# tiles.net
KiCad netlist of a schematic drawn in EAGLE
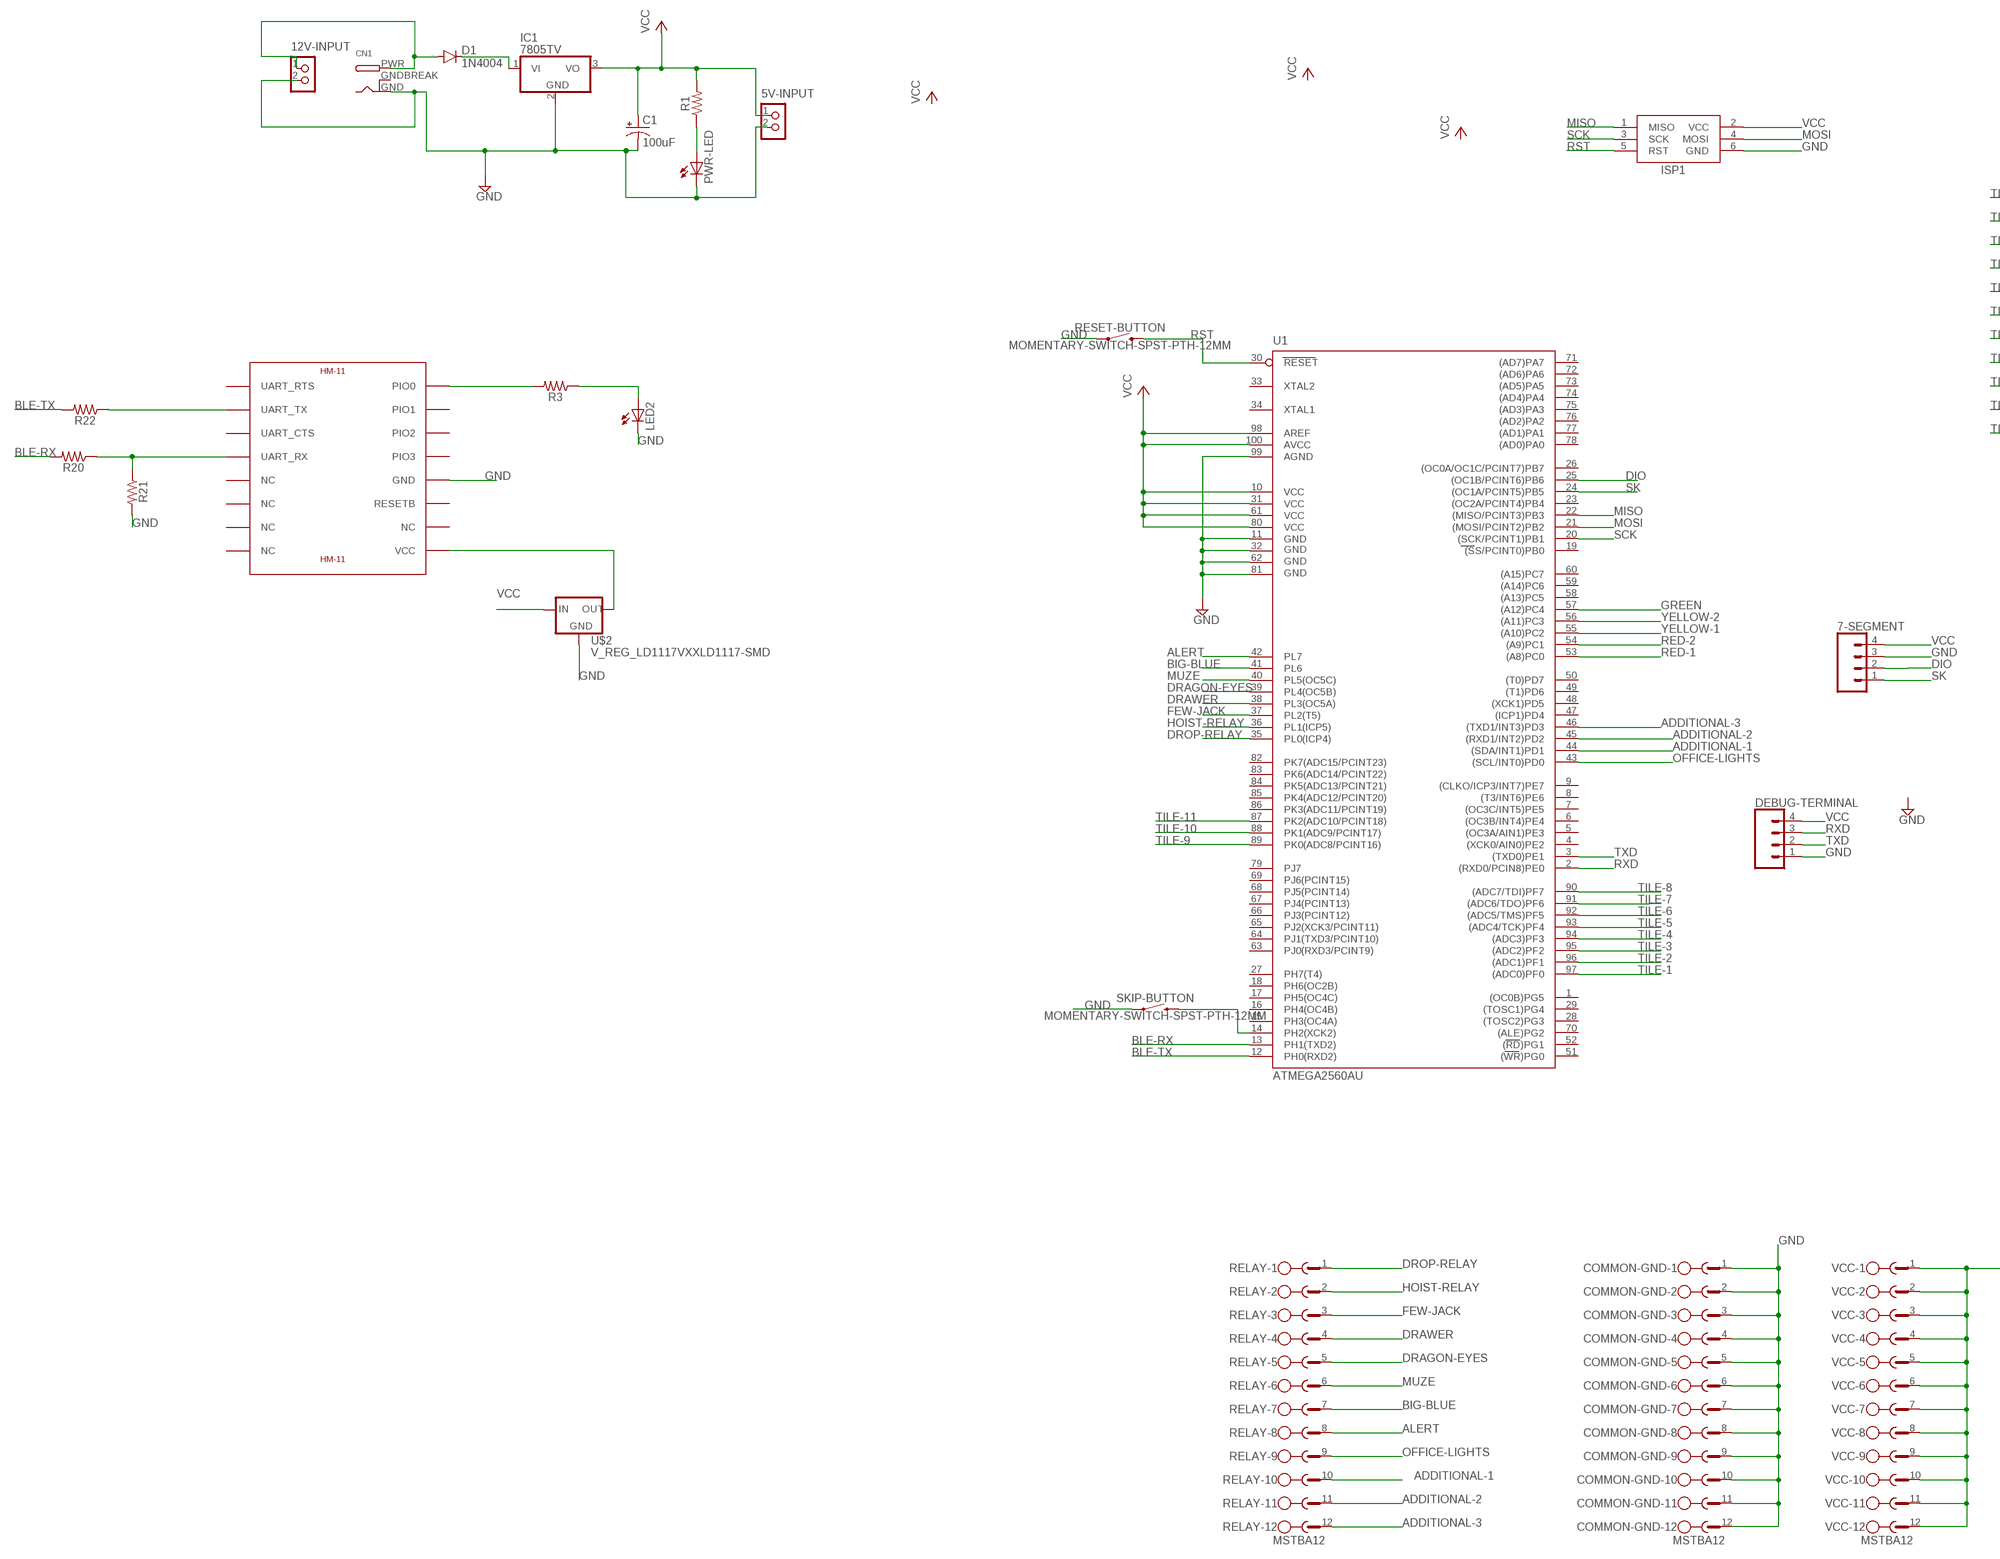
[diagram p0: schematic, sheet 1, part 1 of 2]
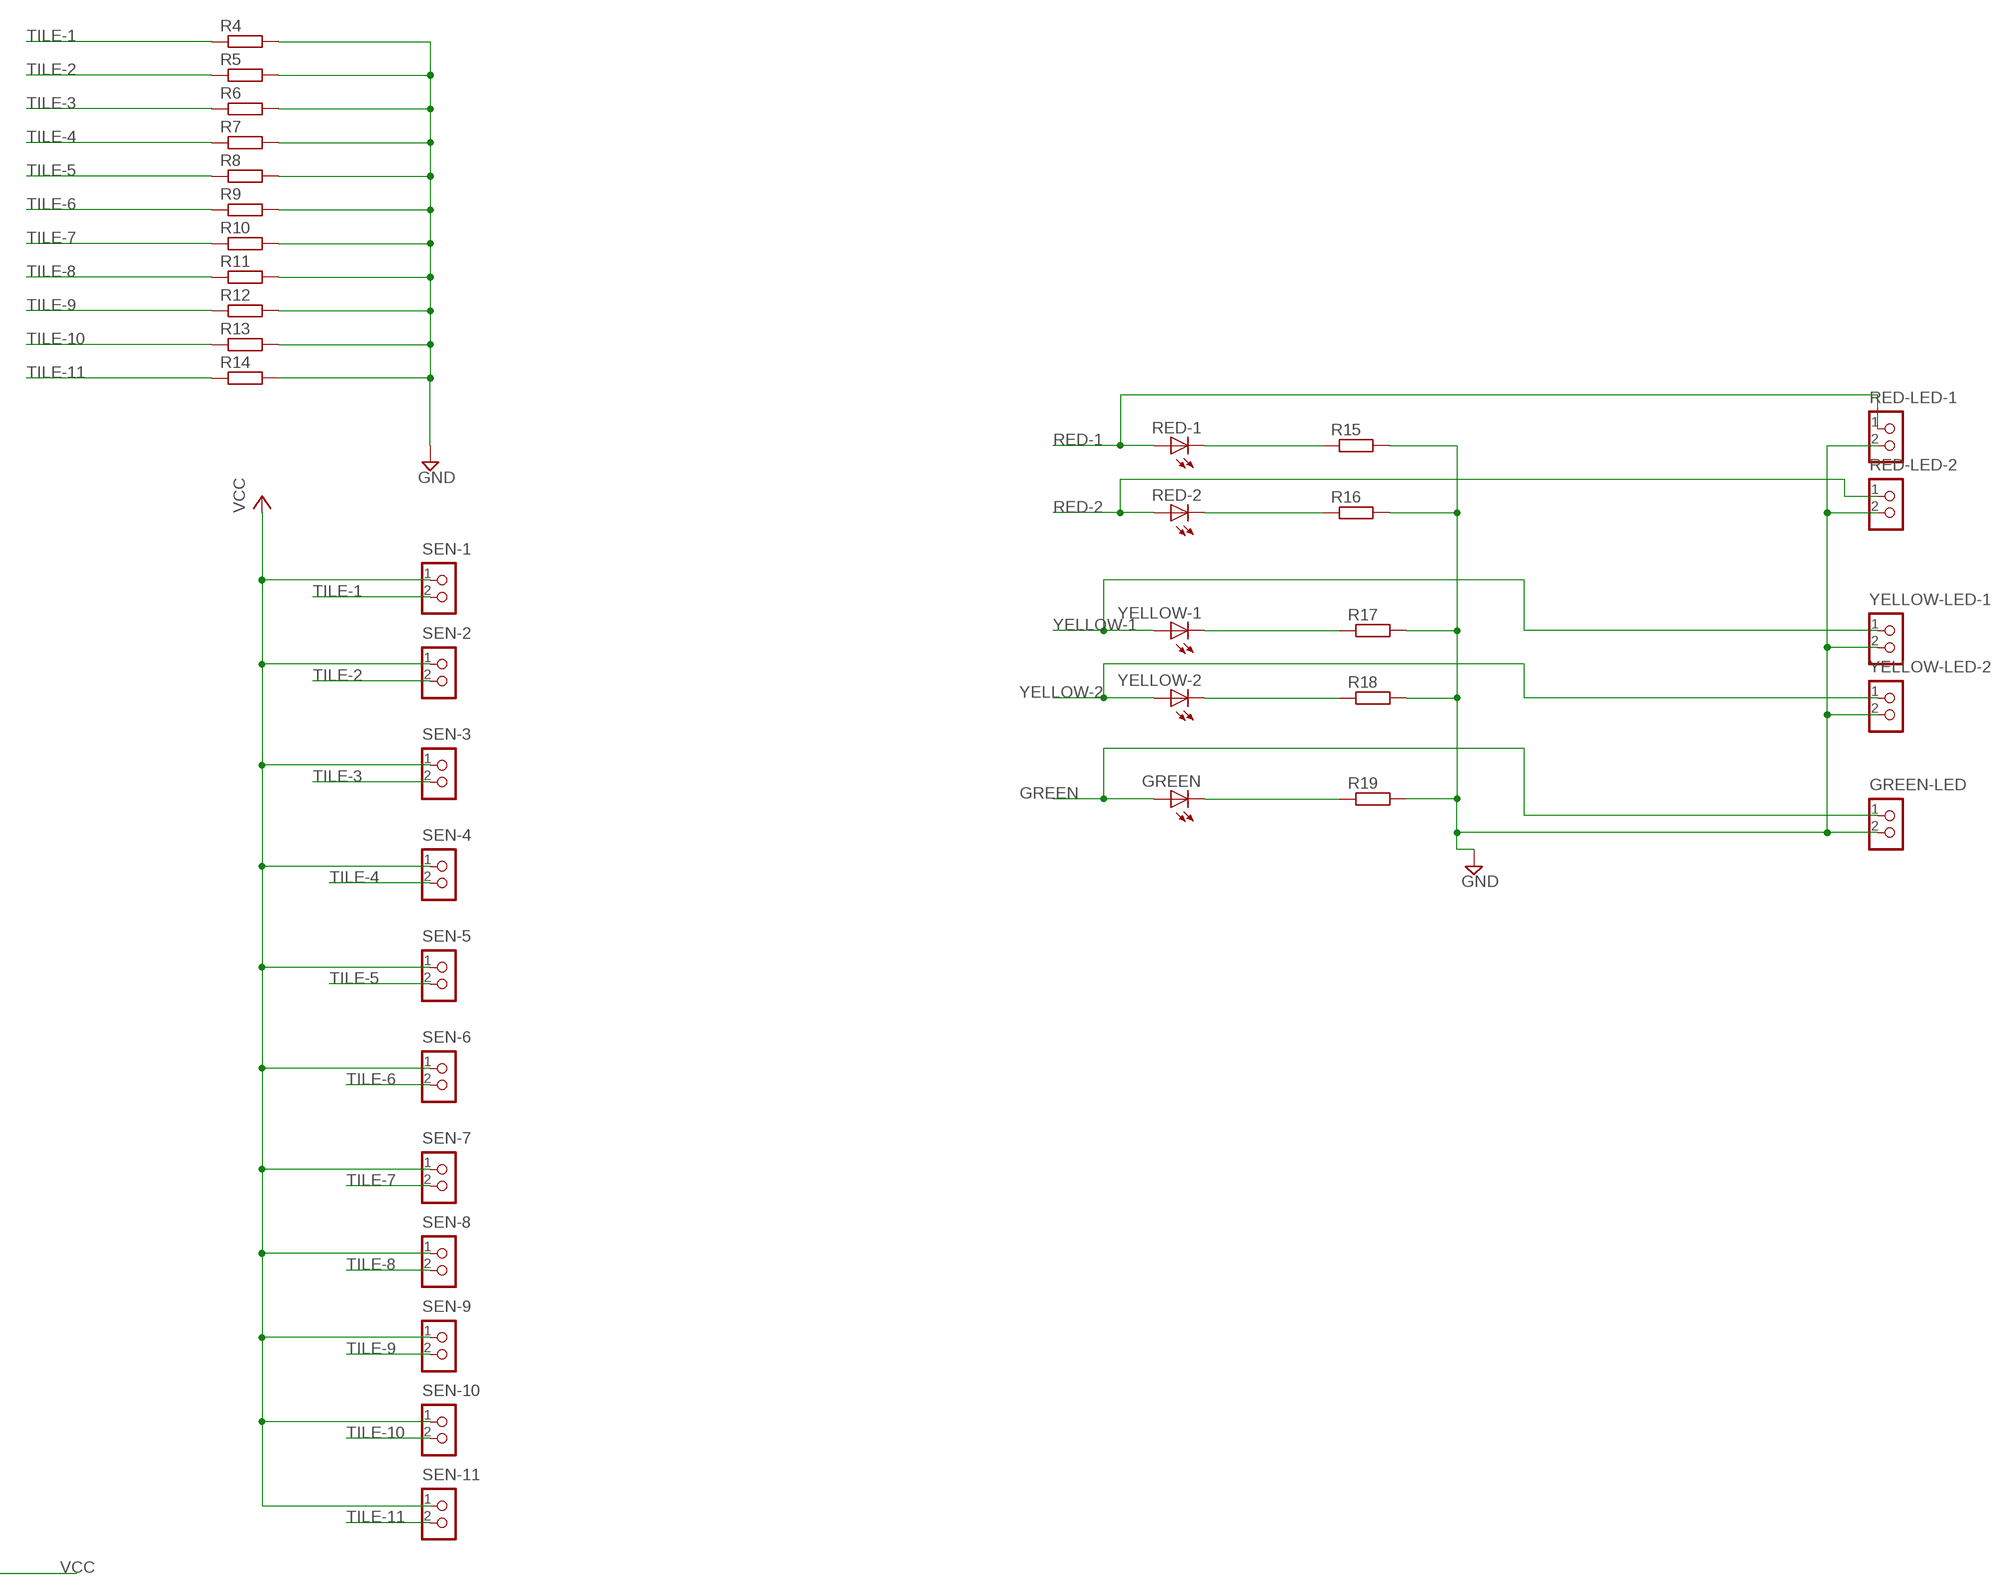
[diagram p1: schematic, sheet 1, part 2 of 2]

(export (version "E")
  (design (tool "Eeschema 10.0.6"))
  (components
    (comp (ref "5V-INPUT")
      (value "CON_TERMINAL_BLOCK_02-5MM")
      (footprint "eagle-import:TERMINAL_BLOCK_2P_5")
      (libsource (lib "eagle-import") (part "CON_TERMINAL_BLOCK_02-5MM"))
    )
    (comp (ref "7-SEGMENT")
      (value "CONN_04PTH")
      (footprint "eagle-import:1X04")
      (libsource (lib "eagle-import") (part "CONN_04PTH"))
    )
    (comp (ref "12V-INPUT")
      (value "CON_TERMINAL_BLOCK_02-5MM")
      (footprint "eagle-import:TERMINAL_BLOCK_2P_5")
      (libsource (lib "eagle-import") (part "CON_TERMINAL_BLOCK_02-5MM"))
    )
    (comp (ref "C1")
      (value "100uF")
      (footprint "eagle-import:CPOL-RADIAL-2.5MM-6.5MM")
      (libsource (lib "eagle-import") (part "100UF-POLAR-RADIAL-2.5MM-25V-20%"))
    )
    (comp (ref "CN1")
      (value "DCBARRELPTH")
      (footprint "eagle-import:DCJACK_2MM_PTH")
      (libsource (lib "eagle-import") (part "DCBARRELPTH"))
    )
    (comp (ref "COMMON-GND")
      (value "MSTBA12")
      (footprint "eagle-import:MSTBA12")
      (fields (field (name "MPN") "1757349"))
      (libsource (lib "eagle-import") (part "MSTBA12"))
    )
    (comp (ref "D1")
      (value "1N4004")
      (footprint "eagle-import:DO41-10")
      (libsource (lib "eagle-import") (part "1N4004"))
    )
    (comp (ref "DEBUG-TERMINAL")
      (value "CONN_04PTH")
      (footprint "eagle-import:1X04")
      (libsource (lib "eagle-import") (part "CONN_04PTH"))
    )
    (comp (ref "GREEN")
      (value "LED5MM")
      (footprint "eagle-import:LED5MM")
      (libsource (lib "eagle-import") (part "LED5MM"))
    )
    (comp (ref "GREEN-LED")
      (value "CON_TERMINAL_BLOCK_02-5MM")
      (footprint "eagle-import:TERMINAL_BLOCK_2P_5")
      (libsource (lib "eagle-import") (part "CON_TERMINAL_BLOCK_02-5MM"))
    )
    (comp (ref "IC1")
      (value "7805TV")
      (footprint "eagle-import:TO220V")
      (libsource (lib "eagle-import") (part "78TV05"))
    )
    (comp (ref "ISP1")
      (value "AVRISP-6")
      (footprint "eagle-import:AVRISP")
      (libsource (lib "eagle-import") (part "AVRISP-6"))
    )
    (comp (ref "LED2")
      (value "LED1206")
      (footprint "eagle-import:LED-1206")
      (libsource (lib "eagle-import") (part "LED1206"))
    )
    (comp (ref "PWR-LED")
      (value "LED1206")
      (footprint "eagle-import:LED-1206")
      (libsource (lib "eagle-import") (part "LED1206"))
    )
    (comp (ref "R1")
      (value "RESISTOR1206")
      (footprint "eagle-import:1206")
      (fields (field (name "SPICEPREFIX") "R"))
      (libsource (lib "eagle-import") (part "RESISTOR1206"))
    )
    (comp (ref "R3")
      (value "RESISTOR1206")
      (footprint "eagle-import:1206")
      (fields (field (name "SPICEPREFIX") "R"))
      (libsource (lib "eagle-import") (part "RESISTOR1206"))
    )
    (comp (ref "R4")
      (value "R-EU_0204/7")
      (footprint "eagle-import:0204_7")
      (libsource (lib "eagle-import") (part "R-EU_0204/7"))
    )
    (comp (ref "R5")
      (value "R-EU_0204/7")
      (footprint "eagle-import:0204_7")
      (libsource (lib "eagle-import") (part "R-EU_0204/7"))
    )
    (comp (ref "R6")
      (value "R-EU_0204/7")
      (footprint "eagle-import:0204_7")
      (libsource (lib "eagle-import") (part "R-EU_0204/7"))
    )
    (comp (ref "R7")
      (value "R-EU_0204/7")
      (footprint "eagle-import:0204_7")
      (libsource (lib "eagle-import") (part "R-EU_0204/7"))
    )
    (comp (ref "R8")
      (value "R-EU_0204/7")
      (footprint "eagle-import:0204_7")
      (libsource (lib "eagle-import") (part "R-EU_0204/7"))
    )
    (comp (ref "R9")
      (value "R-EU_0204/7")
      (footprint "eagle-import:0204_7")
      (libsource (lib "eagle-import") (part "R-EU_0204/7"))
    )
    (comp (ref "R10")
      (value "R-EU_0204/7")
      (footprint "eagle-import:0204_7")
      (libsource (lib "eagle-import") (part "R-EU_0204/7"))
    )
    (comp (ref "R11")
      (value "R-EU_0204/7")
      (footprint "eagle-import:0204_7")
      (libsource (lib "eagle-import") (part "R-EU_0204/7"))
    )
    (comp (ref "R12")
      (value "R-EU_0204/7")
      (footprint "eagle-import:0204_7")
      (libsource (lib "eagle-import") (part "R-EU_0204/7"))
    )
    (comp (ref "R13")
      (value "R-EU_0204/7")
      (footprint "eagle-import:0204_7")
      (libsource (lib "eagle-import") (part "R-EU_0204/7"))
    )
    (comp (ref "R14")
      (value "R-EU_0204/7")
      (footprint "eagle-import:0204_7")
      (libsource (lib "eagle-import") (part "R-EU_0204/7"))
    )
    (comp (ref "R15")
      (value "R-EU_0204/7")
      (footprint "eagle-import:0204_7")
      (libsource (lib "eagle-import") (part "R-EU_0204/7"))
    )
    (comp (ref "R16")
      (value "R-EU_0204/7")
      (footprint "eagle-import:0204_7")
      (libsource (lib "eagle-import") (part "R-EU_0204/7"))
    )
    (comp (ref "R17")
      (value "R-EU_0204/7")
      (footprint "eagle-import:0204_7")
      (libsource (lib "eagle-import") (part "R-EU_0204/7"))
    )
    (comp (ref "R18")
      (value "R-EU_0204/7")
      (footprint "eagle-import:0204_7")
      (libsource (lib "eagle-import") (part "R-EU_0204/7"))
    )
    (comp (ref "R19")
      (value "R-EU_0204/7")
      (footprint "eagle-import:0204_7")
      (libsource (lib "eagle-import") (part "R-EU_0204/7"))
    )
    (comp (ref "R20")
      (value "RESISTOR1206")
      (footprint "eagle-import:1206")
      (fields (field (name "SPICEPREFIX") "R"))
      (libsource (lib "eagle-import") (part "RESISTOR1206"))
    )
    (comp (ref "R21")
      (value "RESISTOR1206")
      (footprint "eagle-import:1206")
      (fields (field (name "SPICEPREFIX") "R"))
      (libsource (lib "eagle-import") (part "RESISTOR1206"))
    )
    (comp (ref "R22")
      (value "RESISTOR1206")
      (footprint "eagle-import:1206")
      (fields (field (name "SPICEPREFIX") "R"))
      (libsource (lib "eagle-import") (part "RESISTOR1206"))
    )
    (comp (ref "RED-1")
      (value "LED5MM")
      (footprint "eagle-import:LED5MM")
      (libsource (lib "eagle-import") (part "LED5MM"))
    )
    (comp (ref "RED-2")
      (value "LED5MM")
      (footprint "eagle-import:LED5MM")
      (libsource (lib "eagle-import") (part "LED5MM"))
    )
    (comp (ref "RED-LED-1")
      (value "CON_TERMINAL_BLOCK_02-5MM")
      (footprint "eagle-import:TERMINAL_BLOCK_2P_5")
      (libsource (lib "eagle-import") (part "CON_TERMINAL_BLOCK_02-5MM"))
    )
    (comp (ref "RED-LED-2")
      (value "CON_TERMINAL_BLOCK_02-5MM")
      (footprint "eagle-import:TERMINAL_BLOCK_2P_5")
      (libsource (lib "eagle-import") (part "CON_TERMINAL_BLOCK_02-5MM"))
    )
    (comp (ref "RELAY")
      (value "MSTBA12")
      (footprint "eagle-import:MSTBA12")
      (fields (field (name "MPN") "1757349"))
      (libsource (lib "eagle-import") (part "MSTBA12"))
    )
    (comp (ref "RESET-BUTTON")
      (value "MOMENTARY-SWITCH-SPST-PTH-12MM")
      (footprint "eagle-import:TACTILE_SWITCH_PTH_12MM")
      (libsource (lib "eagle-import") (part "MOMENTARY-SWITCH-SPST-PTH-12MM"))
    )
    (comp (ref "SEN-1")
      (value "CON_TERMINAL_BLOCK_02-5MM")
      (footprint "eagle-import:TERMINAL_BLOCK_2P_5")
      (libsource (lib "eagle-import") (part "CON_TERMINAL_BLOCK_02-5MM"))
    )
    (comp (ref "SEN-2")
      (value "CON_TERMINAL_BLOCK_02-5MM")
      (footprint "eagle-import:TERMINAL_BLOCK_2P_5")
      (libsource (lib "eagle-import") (part "CON_TERMINAL_BLOCK_02-5MM"))
    )
    (comp (ref "SEN-3")
      (value "CON_TERMINAL_BLOCK_02-5MM")
      (footprint "eagle-import:TERMINAL_BLOCK_2P_5")
      (libsource (lib "eagle-import") (part "CON_TERMINAL_BLOCK_02-5MM"))
    )
    (comp (ref "SEN-4")
      (value "CON_TERMINAL_BLOCK_02-5MM")
      (footprint "eagle-import:TERMINAL_BLOCK_2P_5")
      (libsource (lib "eagle-import") (part "CON_TERMINAL_BLOCK_02-5MM"))
    )
    (comp (ref "SEN-5")
      (value "CON_TERMINAL_BLOCK_02-5MM")
      (footprint "eagle-import:TERMINAL_BLOCK_2P_5")
      (libsource (lib "eagle-import") (part "CON_TERMINAL_BLOCK_02-5MM"))
    )
    (comp (ref "SEN-6")
      (value "CON_TERMINAL_BLOCK_02-5MM")
      (footprint "eagle-import:TERMINAL_BLOCK_2P_5")
      (libsource (lib "eagle-import") (part "CON_TERMINAL_BLOCK_02-5MM"))
    )
    (comp (ref "SEN-7")
      (value "CON_TERMINAL_BLOCK_02-5MM")
      (footprint "eagle-import:TERMINAL_BLOCK_2P_5")
      (libsource (lib "eagle-import") (part "CON_TERMINAL_BLOCK_02-5MM"))
    )
    (comp (ref "SEN-8")
      (value "CON_TERMINAL_BLOCK_02-5MM")
      (footprint "eagle-import:TERMINAL_BLOCK_2P_5")
      (libsource (lib "eagle-import") (part "CON_TERMINAL_BLOCK_02-5MM"))
    )
    (comp (ref "SEN-9")
      (value "CON_TERMINAL_BLOCK_02-5MM")
      (footprint "eagle-import:TERMINAL_BLOCK_2P_5")
      (libsource (lib "eagle-import") (part "CON_TERMINAL_BLOCK_02-5MM"))
    )
    (comp (ref "SEN-10")
      (value "CON_TERMINAL_BLOCK_02-5MM")
      (footprint "eagle-import:TERMINAL_BLOCK_2P_5")
      (libsource (lib "eagle-import") (part "CON_TERMINAL_BLOCK_02-5MM"))
    )
    (comp (ref "SEN-11")
      (value "CON_TERMINAL_BLOCK_02-5MM")
      (footprint "eagle-import:TERMINAL_BLOCK_2P_5")
      (libsource (lib "eagle-import") (part "CON_TERMINAL_BLOCK_02-5MM"))
    )
    (comp (ref "SKIP-BUTTON")
      (value "MOMENTARY-SWITCH-SPST-PTH-12MM")
      (footprint "eagle-import:TACTILE_SWITCH_PTH_12MM")
      (libsource (lib "eagle-import") (part "MOMENTARY-SWITCH-SPST-PTH-12MM"))
    )
    (comp (ref "U$1")
      (value "HM-11")
      (footprint "eagle-import:HM-11")
      (libsource (lib "eagle-import") (part "HM-11"))
    )
    (comp (ref "U$2")
      (value "V_REG_LD1117VXXLD1117-SMD")
      (footprint "eagle-import:SOT223")
      (fields (field (name "SPICEPREFIX") "U"))
      (libsource (lib "eagle-import") (part "V_REG_LD1117VXXLD1117-SMD"))
    )
    (comp (ref "U1")
      (value "ATMEGA2560AU")
      (footprint "eagle-import:TQFP100")
      (libsource (lib "eagle-import") (part "ATMEGA2560AU"))
    )
    (comp (ref "VCC")
      (value "MSTBA12")
      (footprint "eagle-import:MSTBA12")
      (fields (field (name "MPN") "1757349"))
      (libsource (lib "eagle-import") (part "MSTBA12"))
    )
    (comp (ref "YELLOW-1")
      (value "LED5MM")
      (footprint "eagle-import:LED5MM")
      (libsource (lib "eagle-import") (part "LED5MM"))
    )
    (comp (ref "YELLOW-2")
      (value "LED5MM")
      (footprint "eagle-import:LED5MM")
      (libsource (lib "eagle-import") (part "LED5MM"))
    )
    (comp (ref "YELLOW-LED-1")
      (value "CON_TERMINAL_BLOCK_02-5MM")
      (footprint "eagle-import:TERMINAL_BLOCK_2P_5")
      (libsource (lib "eagle-import") (part "CON_TERMINAL_BLOCK_02-5MM"))
    )
    (comp (ref "YELLOW-LED-2")
      (value "CON_TERMINAL_BLOCK_02-5MM")
      (footprint "eagle-import:TERMINAL_BLOCK_2P_5")
      (libsource (lib "eagle-import") (part "CON_TERMINAL_BLOCK_02-5MM"))
    )
  )
  (nets
    (net (code "1") (name "/ADDITIONAL-1") (class "Default")
      (node (ref "RELAY") (pin "10") (pinfunction "1_10") (pintype "passive"))
      (node (ref "U1") (pin "44") (pinfunction "(SDA/INT1)PD1_44") (pintype "bidirectional"))
    )
    (net (code "2") (name "/ADDITIONAL-2") (class "Default")
      (node (ref "RELAY") (pin "11") (pinfunction "1_11") (pintype "passive"))
      (node (ref "U1") (pin "45") (pinfunction "(RXD1/INT2)PD2_45") (pintype "bidirectional"))
    )
    (net (code "3") (name "/ADDITIONAL-3") (class "Default")
      (node (ref "RELAY") (pin "12") (pinfunction "1_12") (pintype "passive"))
      (node (ref "U1") (pin "46") (pinfunction "(TXD1/INT3)PD3_46") (pintype "bidirectional"))
    )
    (net (code "4") (name "/ALERT") (class "Default")
      (node (ref "RELAY") (pin "8") (pinfunction "1_8") (pintype "passive"))
      (node (ref "U1") (pin "42") (pinfunction "PL7_42") (pintype "bidirectional"))
    )
    (net (code "5") (name "/BIG-BLUE") (class "Default")
      (node (ref "RELAY") (pin "7") (pinfunction "1_7") (pintype "passive"))
      (node (ref "U1") (pin "41") (pinfunction "PL6_41") (pintype "bidirectional"))
    )
    (net (code "6") (name "/BLE-RX") (class "Default")
      (node (ref "R20") (pin "2") (pinfunction "2_2") (pintype "passive"))
      (node (ref "U1") (pin "13") (pinfunction "PH1(TXD2)_13") (pintype "bidirectional"))
    )
    (net (code "7") (name "/BLE-TX") (class "Default")
      (node (ref "R22") (pin "2") (pinfunction "2_2") (pintype "passive"))
      (node (ref "U1") (pin "12") (pinfunction "PH0(RXD2)_12") (pintype "bidirectional"))
    )
    (net (code "8") (name "/DIO") (class "Default")
      (node (ref "7-SEGMENT") (pin "2") (pinfunction "2_2") (pintype "passive"))
      (node (ref "U1") (pin "25") (pinfunction "(OC1B/PCINT6)PB6_25") (pintype "bidirectional"))
    )
    (net (code "9") (name "/DRAGON-EYES") (class "Default")
      (node (ref "RELAY") (pin "5") (pinfunction "1_5") (pintype "passive"))
      (node (ref "U1") (pin "39") (pinfunction "PL4(OC5B)_39") (pintype "bidirectional"))
    )
    (net (code "10") (name "/DRAWER") (class "Default")
      (node (ref "RELAY") (pin "4") (pinfunction "1_4") (pintype "passive"))
      (node (ref "U1") (pin "38") (pinfunction "PL3(OC5A)_38") (pintype "bidirectional"))
    )
    (net (code "11") (name "/DROP-RELAY") (class "Default")
      (node (ref "RELAY") (pin "1") (pinfunction "1_1") (pintype "passive"))
      (node (ref "U1") (pin "35") (pinfunction "PL0(ICP4)_35") (pintype "bidirectional"))
    )
    (net (code "12") (name "/FEW-JACK") (class "Default")
      (node (ref "RELAY") (pin "3") (pinfunction "1_3") (pintype "passive"))
      (node (ref "U1") (pin "37") (pinfunction "PL2(T5)_37") (pintype "bidirectional"))
    )
    (net (code "13") (name "/GNDBREAK") (class "Default")
      (node (ref "CN1") (pin "GNDBREAK") (pinfunction "GNDBREAK_GNDBREAK") (pintype "power_in"))
    )
    (net (code "14") (name "/GREEN") (class "Default")
      (node (ref "GREEN") (pin "A") (pinfunction "A_A") (pintype "passive"))
      (node (ref "GREEN-LED") (pin "1") (pinfunction "1_1") (pintype "passive"))
      (node (ref "U1") (pin "57") (pinfunction "(A12)PC4_57") (pintype "bidirectional"))
    )
    (net (code "15") (name "/HOIST-RELAY") (class "Default")
      (node (ref "RELAY") (pin "2") (pinfunction "1_2") (pintype "passive"))
      (node (ref "U1") (pin "36") (pinfunction "PL1(ICP5)_36") (pintype "bidirectional"))
    )
    (net (code "16") (name "/MISO") (class "Default")
      (node (ref "ISP1") (pin "1") (pinfunction "MISO_1") (pintype "input"))
      (node (ref "U1") (pin "22") (pinfunction "(MISO/PCINT3)PB3_22") (pintype "bidirectional"))
    )
    (net (code "17") (name "/MOSI") (class "Default")
      (node (ref "ISP1") (pin "4") (pinfunction "MOSI_4") (pintype "output"))
      (node (ref "U1") (pin "21") (pinfunction "(MOSI/PCINT2)PB2_21") (pintype "bidirectional"))
    )
    (net (code "18") (name "/MUZE") (class "Default")
      (node (ref "RELAY") (pin "6") (pinfunction "1_6") (pintype "passive"))
      (node (ref "U1") (pin "40") (pinfunction "PL5(OC5C)_40") (pintype "bidirectional"))
    )
    (net (code "19") (name "/OFFICE-LIGHTS") (class "Default")
      (node (ref "RELAY") (pin "9") (pinfunction "1_9") (pintype "passive"))
      (node (ref "U1") (pin "43") (pinfunction "(SCL/INT0)PD0_43") (pintype "bidirectional"))
    )
    (net (code "20") (name "/RED-1") (class "Default")
      (node (ref "RED-1") (pin "A") (pinfunction "A_A") (pintype "passive"))
      (node (ref "RED-LED-1") (pin "1") (pinfunction "1_1") (pintype "passive"))
      (node (ref "U1") (pin "53") (pinfunction "(A8)PC0_53") (pintype "bidirectional"))
    )
    (net (code "21") (name "/RED-2") (class "Default")
      (node (ref "RED-2") (pin "A") (pinfunction "A_A") (pintype "passive"))
      (node (ref "RED-LED-2") (pin "1") (pinfunction "1_1") (pintype "passive"))
      (node (ref "U1") (pin "54") (pinfunction "(A9)PC1_54") (pintype "bidirectional"))
    )
    (net (code "22") (name "/RST") (class "Default")
      (node (ref "ISP1") (pin "5") (pinfunction "RST_5") (pintype "output"))
      (node (ref "RESET-BUTTON") (pin "3") (pinfunction "2_3") (pintype "passive"))
      (node (ref "U1") (pin "30") (pinfunction "RESET_30") (pintype "input"))
    )
    (net (code "23") (name "/RXD") (class "Default")
      (node (ref "DEBUG-TERMINAL") (pin "3") (pinfunction "3_3") (pintype "passive"))
      (node (ref "U1") (pin "2") (pinfunction "(RXD0/PCIN8)PE0_2") (pintype "bidirectional"))
    )
    (net (code "24") (name "/SCK") (class "Default")
      (node (ref "ISP1") (pin "3") (pinfunction "SCK_3") (pintype "output"))
      (node (ref "U1") (pin "20") (pinfunction "(SCK/PCINT1)PB1_20") (pintype "bidirectional"))
    )
    (net (code "25") (name "/SK") (class "Default")
      (node (ref "7-SEGMENT") (pin "1") (pinfunction "1_1") (pintype "passive"))
      (node (ref "U1") (pin "24") (pinfunction "(OC1A/PCINT5)PB5_24") (pintype "bidirectional"))
    )
    (net (code "26") (name "/TILE-1") (class "Default")
      (node (ref "R4") (pin "1") (pinfunction "1_1") (pintype "passive"))
      (node (ref "SEN-1") (pin "2") (pinfunction "2_2") (pintype "passive"))
      (node (ref "U1") (pin "97") (pinfunction "(ADC0)PF0_97") (pintype "bidirectional"))
    )
    (net (code "27") (name "/TILE-2") (class "Default")
      (node (ref "R5") (pin "1") (pinfunction "1_1") (pintype "passive"))
      (node (ref "SEN-2") (pin "2") (pinfunction "2_2") (pintype "passive"))
      (node (ref "U1") (pin "96") (pinfunction "(ADC1)PF1_96") (pintype "bidirectional"))
    )
    (net (code "28") (name "/TILE-3") (class "Default")
      (node (ref "R6") (pin "1") (pinfunction "1_1") (pintype "passive"))
      (node (ref "SEN-3") (pin "2") (pinfunction "2_2") (pintype "passive"))
      (node (ref "U1") (pin "95") (pinfunction "(ADC2)PF2_95") (pintype "bidirectional"))
    )
    (net (code "29") (name "/TILE-4") (class "Default")
      (node (ref "R7") (pin "1") (pinfunction "1_1") (pintype "passive"))
      (node (ref "SEN-4") (pin "2") (pinfunction "2_2") (pintype "passive"))
      (node (ref "U1") (pin "94") (pinfunction "(ADC3)PF3_94") (pintype "bidirectional"))
    )
    (net (code "30") (name "/TILE-5") (class "Default")
      (node (ref "R8") (pin "1") (pinfunction "1_1") (pintype "passive"))
      (node (ref "SEN-5") (pin "2") (pinfunction "2_2") (pintype "passive"))
      (node (ref "U1") (pin "93") (pinfunction "(ADC4/TCK)PF4_93") (pintype "bidirectional"))
    )
    (net (code "31") (name "/TILE-6") (class "Default")
      (node (ref "R9") (pin "1") (pinfunction "1_1") (pintype "passive"))
      (node (ref "SEN-6") (pin "2") (pinfunction "2_2") (pintype "passive"))
      (node (ref "U1") (pin "92") (pinfunction "(ADC5/TMS)PF5_92") (pintype "bidirectional"))
    )
    (net (code "32") (name "/TILE-7") (class "Default")
      (node (ref "R10") (pin "1") (pinfunction "1_1") (pintype "passive"))
      (node (ref "SEN-7") (pin "2") (pinfunction "2_2") (pintype "passive"))
      (node (ref "U1") (pin "91") (pinfunction "(ADC6/TDO)PF6_91") (pintype "bidirectional"))
    )
    (net (code "33") (name "/TILE-8") (class "Default")
      (node (ref "R11") (pin "1") (pinfunction "1_1") (pintype "passive"))
      (node (ref "SEN-8") (pin "2") (pinfunction "2_2") (pintype "passive"))
      (node (ref "U1") (pin "90") (pinfunction "(ADC7/TDI)PF7_90") (pintype "bidirectional"))
    )
    (net (code "34") (name "/TILE-9") (class "Default")
      (node (ref "R12") (pin "1") (pinfunction "1_1") (pintype "passive"))
      (node (ref "SEN-9") (pin "2") (pinfunction "2_2") (pintype "passive"))
      (node (ref "U1") (pin "89") (pinfunction "PK0(ADC8/PCINT16)_89") (pintype "bidirectional"))
    )
    (net (code "35") (name "/TILE-10") (class "Default")
      (node (ref "R13") (pin "1") (pinfunction "1_1") (pintype "passive"))
      (node (ref "SEN-10") (pin "2") (pinfunction "2_2") (pintype "passive"))
      (node (ref "U1") (pin "88") (pinfunction "PK1(ADC9/PCINT17)_88") (pintype "bidirectional"))
    )
    (net (code "36") (name "/TILE-11") (class "Default")
      (node (ref "R14") (pin "1") (pinfunction "1_1") (pintype "passive"))
      (node (ref "SEN-11") (pin "2") (pinfunction "2_2") (pintype "passive"))
      (node (ref "U1") (pin "87") (pinfunction "PK2(ADC10/PCINT18)_87") (pintype "bidirectional"))
    )
    (net (code "37") (name "/TXD") (class "Default")
      (node (ref "DEBUG-TERMINAL") (pin "2") (pinfunction "2_2") (pintype "passive"))
      (node (ref "U1") (pin "3") (pinfunction "(TXD0)PE1_3") (pintype "bidirectional"))
    )
    (net (code "38") (name "/YELLOW-1") (class "Default")
      (node (ref "U1") (pin "55") (pinfunction "(A10)PC2_55") (pintype "bidirectional"))
      (node (ref "YELLOW-1") (pin "A") (pinfunction "A_A") (pintype "passive"))
      (node (ref "YELLOW-LED-1") (pin "1") (pinfunction "1_1") (pintype "passive"))
    )
    (net (code "39") (name "/YELLOW-2") (class "Default")
      (node (ref "U1") (pin "56") (pinfunction "(A11)PC3_56") (pintype "bidirectional"))
      (node (ref "YELLOW-2") (pin "A") (pinfunction "A_A") (pintype "passive"))
      (node (ref "YELLOW-LED-2") (pin "1") (pinfunction "1_1") (pintype "passive"))
    )
    (net (code "40") (name "GND") (class "Default")
      (node (ref "12V-INPUT") (pin "2") (pinfunction "2_2") (pintype "passive"))
      (node (ref "5V-INPUT") (pin "2") (pinfunction "2_2") (pintype "passive"))
      (node (ref "7-SEGMENT") (pin "3") (pinfunction "3_3") (pintype "passive"))
      (node (ref "C1") (pin "2") (pinfunction "-_2") (pintype "passive"))
      (node (ref "CN1") (pin "GND") (pinfunction "GND_GND") (pintype "power_in"))
      (node (ref "COMMON-GND") (pin "1") (pinfunction "1_1") (pintype "passive"))
      (node (ref "COMMON-GND") (pin "10") (pinfunction "1_10") (pintype "passive"))
      (node (ref "COMMON-GND") (pin "11") (pinfunction "1_11") (pintype "passive"))
      (node (ref "COMMON-GND") (pin "12") (pinfunction "1_12") (pintype "passive"))
      (node (ref "COMMON-GND") (pin "2") (pinfunction "1_2") (pintype "passive"))
      (node (ref "COMMON-GND") (pin "3") (pinfunction "1_3") (pintype "passive"))
      (node (ref "COMMON-GND") (pin "4") (pinfunction "1_4") (pintype "passive"))
      (node (ref "COMMON-GND") (pin "5") (pinfunction "1_5") (pintype "passive"))
      (node (ref "COMMON-GND") (pin "6") (pinfunction "1_6") (pintype "passive"))
      (node (ref "COMMON-GND") (pin "7") (pinfunction "1_7") (pintype "passive"))
      (node (ref "COMMON-GND") (pin "8") (pinfunction "1_8") (pintype "passive"))
      (node (ref "COMMON-GND") (pin "9") (pinfunction "1_9") (pintype "passive"))
      (node (ref "DEBUG-TERMINAL") (pin "1") (pinfunction "1_1") (pintype "passive"))
      (node (ref "GREEN-LED") (pin "2") (pinfunction "2_2") (pintype "passive"))
      (node (ref "IC1") (pin "2") (pinfunction "GND_2") (pintype "passive"))
      (node (ref "ISP1") (pin "6") (pinfunction "GND_6") (pintype "power_in"))
      (node (ref "LED2") (pin "C") (pinfunction "C_C") (pintype "passive"))
      (node (ref "PWR-LED") (pin "C") (pinfunction "C_C") (pintype "passive"))
      (node (ref "R10") (pin "2") (pinfunction "2_2") (pintype "passive"))
      (node (ref "R11") (pin "2") (pinfunction "2_2") (pintype "passive"))
      (node (ref "R12") (pin "2") (pinfunction "2_2") (pintype "passive"))
      (node (ref "R13") (pin "2") (pinfunction "2_2") (pintype "passive"))
      (node (ref "R14") (pin "2") (pinfunction "2_2") (pintype "passive"))
      (node (ref "R15") (pin "2") (pinfunction "2_2") (pintype "passive"))
      (node (ref "R16") (pin "2") (pinfunction "2_2") (pintype "passive"))
      (node (ref "R17") (pin "2") (pinfunction "2_2") (pintype "passive"))
      (node (ref "R18") (pin "2") (pinfunction "2_2") (pintype "passive"))
      (node (ref "R19") (pin "2") (pinfunction "2_2") (pintype "passive"))
      (node (ref "R21") (pin "2") (pinfunction "2_2") (pintype "passive"))
      (node (ref "R4") (pin "2") (pinfunction "2_2") (pintype "passive"))
      (node (ref "R5") (pin "2") (pinfunction "2_2") (pintype "passive"))
      (node (ref "R6") (pin "2") (pinfunction "2_2") (pintype "passive"))
      (node (ref "R7") (pin "2") (pinfunction "2_2") (pintype "passive"))
      (node (ref "R8") (pin "2") (pinfunction "2_2") (pintype "passive"))
      (node (ref "R9") (pin "2") (pinfunction "2_2") (pintype "passive"))
      (node (ref "RED-LED-1") (pin "2") (pinfunction "2_2") (pintype "passive"))
      (node (ref "RED-LED-2") (pin "2") (pinfunction "2_2") (pintype "passive"))
      (node (ref "RESET-BUTTON") (pin "1") (pinfunction "1_1") (pintype "passive"))
      (node (ref "SKIP-BUTTON") (pin "1") (pinfunction "1_1") (pintype "passive"))
      (node (ref "U$1") (pin "GND") (pinfunction "GND_GND") (pintype "bidirectional"))
      (node (ref "U$2") (pin "1") (pinfunction "GND_1") (pintype "input"))
      (node (ref "U1") (pin "11") (pinfunction "GND_11") (pintype "power_in"))
      (node (ref "U1") (pin "32") (pinfunction "GND1_32") (pintype "power_in"))
      (node (ref "U1") (pin "62") (pinfunction "GND2_62") (pintype "power_in"))
      (node (ref "U1") (pin "81") (pinfunction "GND3_81") (pintype "power_in"))
      (node (ref "U1") (pin "99") (pinfunction "AGND_99") (pintype "power_in"))
      (node (ref "YELLOW-LED-1") (pin "2") (pinfunction "2_2") (pintype "passive"))
      (node (ref "YELLOW-LED-2") (pin "2") (pinfunction "2_2") (pintype "passive"))
    )
    (net (code "41") (name "Net-(12V-INPUT-Pad1)") (class "Default")
      (node (ref "12V-INPUT") (pin "1") (pinfunction "1_1") (pintype "passive"))
      (node (ref "CN1") (pin "PWR") (pinfunction "PWR_PWR") (pintype "power_in"))
      (node (ref "D1") (pin "A") (pinfunction "A_A") (pintype "passive"))
    )
    (net (code "42") (name "Net-(GREEN-C)") (class "Default")
      (node (ref "GREEN") (pin "K") (pinfunction "C_K") (pintype "passive"))
      (node (ref "R19") (pin "1") (pinfunction "1_1") (pintype "passive"))
    )
    (net (code "43") (name "Net-(IC1-VI)") (class "Default")
      (node (ref "D1") (pin "C") (pinfunction "C_C") (pintype "passive"))
      (node (ref "IC1") (pin "1") (pinfunction "VI_1") (pintype "input"))
    )
    (net (code "44") (name "Net-(LED2-PadA)") (class "Default")
      (node (ref "LED2") (pin "A") (pinfunction "A_A") (pintype "passive"))
      (node (ref "R3") (pin "1") (pinfunction "1_1") (pintype "passive"))
    )
    (net (code "45") (name "Net-(PWR-LED-PadA)") (class "Default")
      (node (ref "PWR-LED") (pin "A") (pinfunction "A_A") (pintype "passive"))
      (node (ref "R1") (pin "1") (pinfunction "1_1") (pintype "passive"))
    )
    (net (code "46") (name "Net-(R3-Pad2)") (class "Default")
      (node (ref "R3") (pin "2") (pinfunction "2_2") (pintype "passive"))
      (node (ref "U$1") (pin "PIO0") (pinfunction "PIO0_PIO0") (pintype "bidirectional"))
    )
    (net (code "47") (name "Net-(R20-Pad1)") (class "Default")
      (node (ref "R20") (pin "1") (pinfunction "1_1") (pintype "passive"))
      (node (ref "R21") (pin "1") (pinfunction "1_1") (pintype "passive"))
      (node (ref "U$1") (pin "UART_RX") (pinfunction "UART_RX_UART_RX") (pintype "bidirectional"))
    )
    (net (code "48") (name "Net-(R22-Pad1)") (class "Default")
      (node (ref "R22") (pin "1") (pinfunction "1_1") (pintype "passive"))
      (node (ref "U$1") (pin "UART_TX") (pinfunction "UART_TX_UART_TX") (pintype "bidirectional"))
    )
    (net (code "49") (name "Net-(RED-1-C)") (class "Default")
      (node (ref "R15") (pin "1") (pinfunction "1_1") (pintype "passive"))
      (node (ref "RED-1") (pin "K") (pinfunction "C_K") (pintype "passive"))
    )
    (net (code "50") (name "Net-(RED-2-C)") (class "Default")
      (node (ref "R16") (pin "1") (pinfunction "1_1") (pintype "passive"))
      (node (ref "RED-2") (pin "K") (pinfunction "C_K") (pintype "passive"))
    )
    (net (code "51") (name "Net-(SKIP-BUTTON-2)") (class "Default")
      (node (ref "SKIP-BUTTON") (pin "3") (pinfunction "2_3") (pintype "passive"))
      (node (ref "U1") (pin "14") (pinfunction "PH2(XCK2)_14") (pintype "bidirectional"))
    )
    (net (code "52") (name "Net-(U$2-OUT)") (class "Default")
      (node (ref "U$1") (pin "VCC") (pinfunction "VCC_VCC") (pintype "bidirectional"))
      (node (ref "U$2") (pin "2") (pinfunction "OUT_2") (pintype "passive"))
    )
    (net (code "53") (name "Net-(YELLOW-1-C)") (class "Default")
      (node (ref "R17") (pin "1") (pinfunction "1_1") (pintype "passive"))
      (node (ref "YELLOW-1") (pin "K") (pinfunction "C_K") (pintype "passive"))
    )
    (net (code "54") (name "Net-(YELLOW-2-C)") (class "Default")
      (node (ref "R18") (pin "1") (pinfunction "1_1") (pintype "passive"))
      (node (ref "YELLOW-2") (pin "K") (pinfunction "C_K") (pintype "passive"))
    )
    (net (code "55") (name "VCC") (class "Default")
      (node (ref "5V-INPUT") (pin "1") (pinfunction "1_1") (pintype "passive"))
      (node (ref "7-SEGMENT") (pin "4") (pinfunction "4_4") (pintype "passive"))
      (node (ref "C1") (pin "1") (pinfunction "+_1") (pintype "passive"))
      (node (ref "DEBUG-TERMINAL") (pin "4") (pinfunction "4_4") (pintype "passive"))
      (node (ref "IC1") (pin "3") (pinfunction "VO_3") (pintype "passive"))
      (node (ref "ISP1") (pin "2") (pinfunction "VCC_2") (pintype "power_in"))
      (node (ref "R1") (pin "2") (pinfunction "2_2") (pintype "passive"))
      (node (ref "SEN-1") (pin "1") (pinfunction "1_1") (pintype "passive"))
      (node (ref "SEN-10") (pin "1") (pinfunction "1_1") (pintype "passive"))
      (node (ref "SEN-11") (pin "1") (pinfunction "1_1") (pintype "passive"))
      (node (ref "SEN-2") (pin "1") (pinfunction "1_1") (pintype "passive"))
      (node (ref "SEN-3") (pin "1") (pinfunction "1_1") (pintype "passive"))
      (node (ref "SEN-4") (pin "1") (pinfunction "1_1") (pintype "passive"))
      (node (ref "SEN-5") (pin "1") (pinfunction "1_1") (pintype "passive"))
      (node (ref "SEN-6") (pin "1") (pinfunction "1_1") (pintype "passive"))
      (node (ref "SEN-7") (pin "1") (pinfunction "1_1") (pintype "passive"))
      (node (ref "SEN-8") (pin "1") (pinfunction "1_1") (pintype "passive"))
      (node (ref "SEN-9") (pin "1") (pinfunction "1_1") (pintype "passive"))
      (node (ref "U$2") (pin "3") (pinfunction "IN_3") (pintype "input"))
      (node (ref "U1") (pin "10") (pinfunction "VCC_10") (pintype "power_in"))
      (node (ref "U1") (pin "100") (pinfunction "AVCC_100") (pintype "power_in"))
      (node (ref "U1") (pin "31") (pinfunction "VCC1_31") (pintype "power_in"))
      (node (ref "U1") (pin "61") (pinfunction "VCC2_61") (pintype "power_in"))
      (node (ref "U1") (pin "80") (pinfunction "VCC3_80") (pintype "power_in"))
      (node (ref "U1") (pin "98") (pinfunction "AREF_98") (pintype "bidirectional"))
      (node (ref "VCC") (pin "1") (pinfunction "1_1") (pintype "passive"))
      (node (ref "VCC") (pin "10") (pinfunction "1_10") (pintype "passive"))
      (node (ref "VCC") (pin "11") (pinfunction "1_11") (pintype "passive"))
      (node (ref "VCC") (pin "12") (pinfunction "1_12") (pintype "passive"))
      (node (ref "VCC") (pin "2") (pinfunction "1_2") (pintype "passive"))
      (node (ref "VCC") (pin "3") (pinfunction "1_3") (pintype "passive"))
      (node (ref "VCC") (pin "4") (pinfunction "1_4") (pintype "passive"))
      (node (ref "VCC") (pin "5") (pinfunction "1_5") (pintype "passive"))
      (node (ref "VCC") (pin "6") (pinfunction "1_6") (pintype "passive"))
      (node (ref "VCC") (pin "7") (pinfunction "1_7") (pintype "passive"))
      (node (ref "VCC") (pin "8") (pinfunction "1_8") (pintype "passive"))
      (node (ref "VCC") (pin "9") (pinfunction "1_9") (pintype "passive"))
    )
    (net (code "56") (name "unconnected-(U$1-NC-PadNC@5)") (class "Default")
      (node (ref "U$1") (pin "NC@5") (pinfunction "NC_NC@5") (pintype "bidirectional"))
    )
    (net (code "57") (name "unconnected-(U$1-NC-PadNC@6)") (class "Default")
      (node (ref "U$1") (pin "NC@6") (pinfunction "NC_NC@6") (pintype "bidirectional"))
    )
    (net (code "58") (name "unconnected-(U$1-NC-PadNC@7)") (class "Default")
      (node (ref "U$1") (pin "NC@7") (pinfunction "NC_NC@7") (pintype "bidirectional"))
    )
    (net (code "59") (name "unconnected-(U$1-NC-PadNC@8)") (class "Default")
      (node (ref "U$1") (pin "NC@8") (pinfunction "NC_NC@8") (pintype "bidirectional"))
    )
    (net (code "60") (name "unconnected-(U$1-NC-PadNC@10)") (class "Default")
      (node (ref "U$1") (pin "NC@10") (pinfunction "NC_NC@10") (pintype "bidirectional"))
    )
    (net (code "61") (name "unconnected-(U$1-PadPIO1)") (class "Default")
      (node (ref "U$1") (pin "PIO1") (pinfunction "PIO1_PIO1") (pintype "bidirectional"))
    )
    (net (code "62") (name "unconnected-(U$1-PadPIO2)") (class "Default")
      (node (ref "U$1") (pin "PIO2") (pinfunction "PIO2_PIO2") (pintype "bidirectional"))
    )
    (net (code "63") (name "unconnected-(U$1-PadPIO3)") (class "Default")
      (node (ref "U$1") (pin "PIO3") (pinfunction "PIO3_PIO3") (pintype "bidirectional"))
    )
    (net (code "64") (name "unconnected-(U$1-PadRESETB)") (class "Default")
      (node (ref "U$1") (pin "RESETB") (pinfunction "RESETB_RESETB") (pintype "bidirectional"))
    )
    (net (code "65") (name "unconnected-(U$1-PadUART_CTS)") (class "Default")
      (node (ref "U$1") (pin "UART_CTS") (pinfunction "UART_CTS_UART_CTS") (pintype "bidirectional"))
    )
    (net (code "66") (name "unconnected-(U$1-PadUART_RTS)") (class "Default")
      (node (ref "U$1") (pin "UART_RTS") (pinfunction "UART_RTS_UART_RTS") (pintype "bidirectional"))
    )
    (net (code "67") (name "unconnected-(U1-(A13)PC5-Pad58)") (class "Default")
      (node (ref "U1") (pin "58") (pinfunction "(A13)PC5_58") (pintype "bidirectional"))
    )
    (net (code "68") (name "unconnected-(U1-(A14)PC6-Pad59)") (class "Default")
      (node (ref "U1") (pin "59") (pinfunction "(A14)PC6_59") (pintype "bidirectional"))
    )
    (net (code "69") (name "unconnected-(U1-(A15)PC7-Pad60)") (class "Default")
      (node (ref "U1") (pin "60") (pinfunction "(A15)PC7_60") (pintype "bidirectional"))
    )
    (net (code "70") (name "unconnected-(U1-(AD0)PA0-Pad78)") (class "Default")
      (node (ref "U1") (pin "78") (pinfunction "(AD0)PA0_78") (pintype "bidirectional"))
    )
    (net (code "71") (name "unconnected-(U1-(AD1)PA1-Pad77)") (class "Default")
      (node (ref "U1") (pin "77") (pinfunction "(AD1)PA1_77") (pintype "bidirectional"))
    )
    (net (code "72") (name "unconnected-(U1-(AD2)PA2-Pad76)") (class "Default")
      (node (ref "U1") (pin "76") (pinfunction "(AD2)PA2_76") (pintype "bidirectional"))
    )
    (net (code "73") (name "unconnected-(U1-(AD3)PA3-Pad75)") (class "Default")
      (node (ref "U1") (pin "75") (pinfunction "(AD3)PA3_75") (pintype "bidirectional"))
    )
    (net (code "74") (name "unconnected-(U1-(AD4)PA4-Pad74)") (class "Default")
      (node (ref "U1") (pin "74") (pinfunction "(AD4)PA4_74") (pintype "bidirectional"))
    )
    (net (code "75") (name "unconnected-(U1-(AD5)PA5-Pad73)") (class "Default")
      (node (ref "U1") (pin "73") (pinfunction "(AD5)PA5_73") (pintype "bidirectional"))
    )
    (net (code "76") (name "unconnected-(U1-(AD6)PA6-Pad72)") (class "Default")
      (node (ref "U1") (pin "72") (pinfunction "(AD6)PA6_72") (pintype "bidirectional"))
    )
    (net (code "77") (name "unconnected-(U1-(AD7)PA7-Pad71)") (class "Default")
      (node (ref "U1") (pin "71") (pinfunction "(AD7)PA7_71") (pintype "bidirectional"))
    )
    (net (code "78") (name "unconnected-(U1-(ALE)PG2-Pad70)") (class "Default")
      (node (ref "U1") (pin "70") (pinfunction "(ALE)PG2_70") (pintype "bidirectional"))
    )
    (net (code "79") (name "unconnected-(U1-(CLKO{slash}ICP3{slash}INT7)PE7-Pad9)") (class "Default")
      (node (ref "U1") (pin "9") (pinfunction "(CLKO/ICP3/INT7)PE7_9") (pintype "bidirectional"))
    )
    (net (code "80") (name "unconnected-(U1-(ICP1)PD4-Pad47)") (class "Default")
      (node (ref "U1") (pin "47") (pinfunction "(ICP1)PD4_47") (pintype "bidirectional"))
    )
    (net (code "81") (name "unconnected-(U1-(OC0A{slash}OC1C{slash}PCINT7)PB7-Pad26)") (class "Default")
      (node (ref "U1") (pin "26") (pinfunction "(OC0A/OC1C/PCINT7)PB7_26") (pintype "bidirectional"))
    )
    (net (code "82") (name "unconnected-(U1-(OC0B)PG5-Pad1)") (class "Default")
      (node (ref "U1") (pin "1") (pinfunction "(OC0B)PG5_1") (pintype "bidirectional"))
    )
    (net (code "83") (name "unconnected-(U1-(OC2A{slash}PCINT4)PB4-Pad23)") (class "Default")
      (node (ref "U1") (pin "23") (pinfunction "(OC2A/PCINT4)PB4_23") (pintype "bidirectional"))
    )
    (net (code "84") (name "unconnected-(U1-(OC3A{slash}AIN1)PE3-Pad5)") (class "Default")
      (node (ref "U1") (pin "5") (pinfunction "(OC3A/AIN1)PE3_5") (pintype "bidirectional"))
    )
    (net (code "85") (name "unconnected-(U1-(OC3B{slash}INT4)PE4-Pad6)") (class "Default")
      (node (ref "U1") (pin "6") (pinfunction "(OC3B/INT4)PE4_6") (pintype "bidirectional"))
    )
    (net (code "86") (name "unconnected-(U1-(OC3C{slash}INT5)PE5-Pad7)") (class "Default")
      (node (ref "U1") (pin "7") (pinfunction "(OC3C/INT5)PE5_7") (pintype "bidirectional"))
    )
    (net (code "87") (name "unconnected-(U1-(RD)PG1-Pad52)") (class "Default")
      (node (ref "U1") (pin "52") (pinfunction "(RD)PG1_52") (pintype "bidirectional"))
    )
    (net (code "88") (name "unconnected-(U1-(SS{slash}PCINT0)PB0-Pad19)") (class "Default")
      (node (ref "U1") (pin "19") (pinfunction "(SS/PCINT0)PB0_19") (pintype "bidirectional"))
    )
    (net (code "89") (name "unconnected-(U1-(T0)PD7-Pad50)") (class "Default")
      (node (ref "U1") (pin "50") (pinfunction "(T0)PD7_50") (pintype "bidirectional"))
    )
    (net (code "90") (name "unconnected-(U1-(T1)PD6-Pad49)") (class "Default")
      (node (ref "U1") (pin "49") (pinfunction "(T1)PD6_49") (pintype "bidirectional"))
    )
    (net (code "91") (name "unconnected-(U1-(T3{slash}INT6)PE6-Pad8)") (class "Default")
      (node (ref "U1") (pin "8") (pinfunction "(T3/INT6)PE6_8") (pintype "bidirectional"))
    )
    (net (code "92") (name "unconnected-(U1-(TOSC1)PG4-Pad29)") (class "Default")
      (node (ref "U1") (pin "29") (pinfunction "(TOSC1)PG4_29") (pintype "bidirectional"))
    )
    (net (code "93") (name "unconnected-(U1-(TOSC2)PG3-Pad28)") (class "Default")
      (node (ref "U1") (pin "28") (pinfunction "(TOSC2)PG3_28") (pintype "bidirectional"))
    )
    (net (code "94") (name "unconnected-(U1-(WR)PG0-Pad51)") (class "Default")
      (node (ref "U1") (pin "51") (pinfunction "(WR)PG0_51") (pintype "bidirectional"))
    )
    (net (code "95") (name "unconnected-(U1-(XCK0{slash}AIN0)PE2-Pad4)") (class "Default")
      (node (ref "U1") (pin "4") (pinfunction "(XCK0/AIN0)PE2_4") (pintype "bidirectional"))
    )
    (net (code "96") (name "unconnected-(U1-(XCK1)PD5-Pad48)") (class "Default")
      (node (ref "U1") (pin "48") (pinfunction "(XCK1)PD5_48") (pintype "bidirectional"))
    )
    (net (code "97") (name "unconnected-(U1-PH3(OC4A)-Pad15)") (class "Default")
      (node (ref "U1") (pin "15") (pinfunction "PH3(OC4A)_15") (pintype "bidirectional"))
    )
    (net (code "98") (name "unconnected-(U1-PH4(OC4B)-Pad16)") (class "Default")
      (node (ref "U1") (pin "16") (pinfunction "PH4(OC4B)_16") (pintype "bidirectional"))
    )
    (net (code "99") (name "unconnected-(U1-PH5(OC4C)-Pad17)") (class "Default")
      (node (ref "U1") (pin "17") (pinfunction "PH5(OC4C)_17") (pintype "bidirectional"))
    )
    (net (code "100") (name "unconnected-(U1-PH6(OC2B)-Pad18)") (class "Default")
      (node (ref "U1") (pin "18") (pinfunction "PH6(OC2B)_18") (pintype "bidirectional"))
    )
    (net (code "101") (name "unconnected-(U1-PH7(T4)-Pad27)") (class "Default")
      (node (ref "U1") (pin "27") (pinfunction "PH7(T4)_27") (pintype "bidirectional"))
    )
    (net (code "102") (name "unconnected-(U1-PJ0(RXD3{slash}PCINT9)-Pad63)") (class "Default")
      (node (ref "U1") (pin "63") (pinfunction "PJ0(RXD3/PCINT9)_63") (pintype "bidirectional"))
    )
    (net (code "103") (name "unconnected-(U1-PJ1(TXD3{slash}PCINT10)-Pad64)") (class "Default")
      (node (ref "U1") (pin "64") (pinfunction "PJ1(TXD3/PCINT10)_64") (pintype "bidirectional"))
    )
    (net (code "104") (name "unconnected-(U1-PJ2(XCK3{slash}PCINT11)-Pad65)") (class "Default")
      (node (ref "U1") (pin "65") (pinfunction "PJ2(XCK3/PCINT11)_65") (pintype "bidirectional"))
    )
    (net (code "105") (name "unconnected-(U1-PJ3(PCINT12)-Pad66)") (class "Default")
      (node (ref "U1") (pin "66") (pinfunction "PJ3(PCINT12)_66") (pintype "bidirectional"))
    )
    (net (code "106") (name "unconnected-(U1-PJ4(PCINT13)-Pad67)") (class "Default")
      (node (ref "U1") (pin "67") (pinfunction "PJ4(PCINT13)_67") (pintype "bidirectional"))
    )
    (net (code "107") (name "unconnected-(U1-PJ5(PCINT14)-Pad68)") (class "Default")
      (node (ref "U1") (pin "68") (pinfunction "PJ5(PCINT14)_68") (pintype "bidirectional"))
    )
    (net (code "108") (name "unconnected-(U1-PJ6(PCINT15)-Pad69)") (class "Default")
      (node (ref "U1") (pin "69") (pinfunction "PJ6(PCINT15)_69") (pintype "bidirectional"))
    )
    (net (code "109") (name "unconnected-(U1-PJ7-Pad79)") (class "Default")
      (node (ref "U1") (pin "79") (pinfunction "PJ7_79") (pintype "bidirectional"))
    )
    (net (code "110") (name "unconnected-(U1-PK3(ADC11{slash}PCINT19)-Pad86)") (class "Default")
      (node (ref "U1") (pin "86") (pinfunction "PK3(ADC11/PCINT19)_86") (pintype "bidirectional"))
    )
    (net (code "111") (name "unconnected-(U1-PK4(ADC12{slash}PCINT20)-Pad85)") (class "Default")
      (node (ref "U1") (pin "85") (pinfunction "PK4(ADC12/PCINT20)_85") (pintype "bidirectional"))
    )
    (net (code "112") (name "unconnected-(U1-PK5(ADC13{slash}PCINT21)-Pad84)") (class "Default")
      (node (ref "U1") (pin "84") (pinfunction "PK5(ADC13/PCINT21)_84") (pintype "bidirectional"))
    )
    (net (code "113") (name "unconnected-(U1-PK6(ADC14{slash}PCINT22)-Pad83)") (class "Default")
      (node (ref "U1") (pin "83") (pinfunction "PK6(ADC14/PCINT22)_83") (pintype "bidirectional"))
    )
    (net (code "114") (name "unconnected-(U1-PK7(ADC15{slash}PCINT23)-Pad82)") (class "Default")
      (node (ref "U1") (pin "82") (pinfunction "PK7(ADC15/PCINT23)_82") (pintype "bidirectional"))
    )
    (net (code "115") (name "unconnected-(U1-XTAL1-Pad34)") (class "Default")
      (node (ref "U1") (pin "34") (pinfunction "XTAL1_34") (pintype "input"))
    )
    (net (code "116") (name "unconnected-(U1-XTAL2-Pad33)") (class "Default")
      (node (ref "U1") (pin "33") (pinfunction "XTAL2_33") (pintype "output"))
    )
  )
)
